# power_breakout.net
KiCad netlist of a schematic drawn in EAGLE
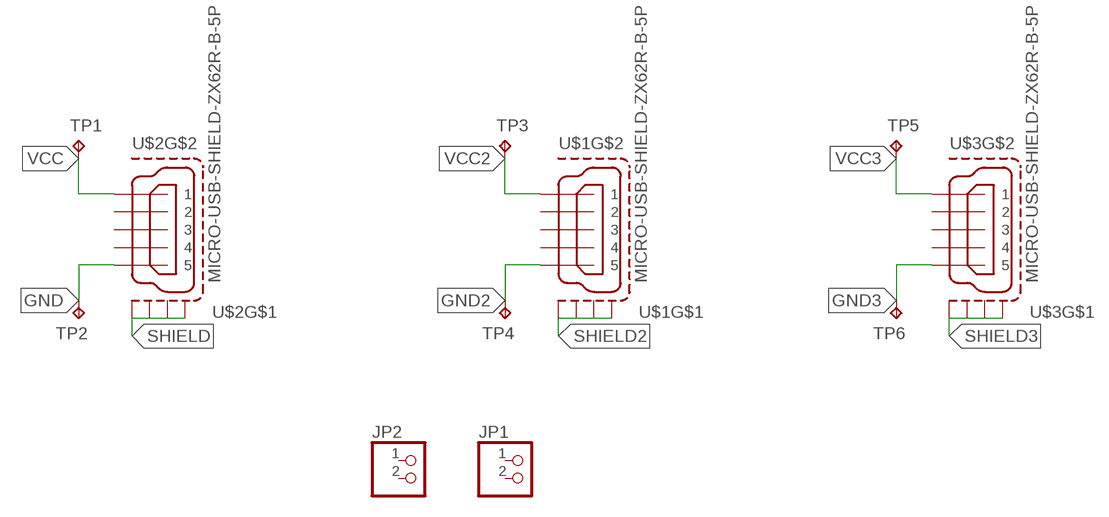
[diagram p0: schematic, sheet 1]

(export (version "E")
  (design (tool "Eeschema 10.0.6"))
  (components
    (comp (ref "JP1")
      (value "PINHD-1X2/90")
      (footprint "eagle-import:1X02_90")
      (libsource (lib "eagle-import") (part "PINHD-1X2/90"))
    )
    (comp (ref "JP2")
      (value "PINHD-1X2/90")
      (footprint "eagle-import:1X02_90")
      (libsource (lib "eagle-import") (part "PINHD-1X2/90"))
    )
    (comp (ref "TP1")
      (value "TPB1,27")
      (footprint "eagle-import:B1,27")
      (libsource (lib "eagle-import") (part "TPB1,27"))
    )
    (comp (ref "TP2")
      (value "TPB1,27")
      (footprint "eagle-import:B1,27")
      (libsource (lib "eagle-import") (part "TPB1,27"))
    )
    (comp (ref "TP3")
      (value "TPB1,27")
      (footprint "eagle-import:B1,27")
      (libsource (lib "eagle-import") (part "TPB1,27"))
    )
    (comp (ref "TP4")
      (value "TPB1,27")
      (footprint "eagle-import:B1,27")
      (libsource (lib "eagle-import") (part "TPB1,27"))
    )
    (comp (ref "TP5")
      (value "TPB1,27")
      (footprint "eagle-import:B1,27")
      (libsource (lib "eagle-import") (part "TPB1,27"))
    )
    (comp (ref "TP6")
      (value "TPB1,27")
      (footprint "eagle-import:B1,27")
      (libsource (lib "eagle-import") (part "TPB1,27"))
    )
    (comp (ref "U$1")
      (value "MICRO-USB-SHIELD-ZX62R-B-5P")
      (footprint "eagle-import:ZX62R-B-5P")
      (libsource (lib "eagle-import") (part "MICRO-USB-SHIELD-ZX62R-B-5P"))
    )
    (comp (ref "U$2")
      (value "MICRO-USB-SHIELD-ZX62R-B-5P")
      (footprint "eagle-import:ZX62R-B-5P")
      (libsource (lib "eagle-import") (part "MICRO-USB-SHIELD-ZX62R-B-5P"))
    )
    (comp (ref "U$3")
      (value "MICRO-USB-SHIELD-ZX62R-B-5P")
      (footprint "eagle-import:ZX62R-B-5P")
      (libsource (lib "eagle-import") (part "MICRO-USB-SHIELD-ZX62R-B-5P"))
    )
  )
  (nets
    (net (code "1") (name "GND") (class "Default")
      (node (ref "TP2") (pin "TP") (pinfunction "TP_TP") (pintype "input"))
      (node (ref "U$2") (pin "5") (pinfunction "5_5") (pintype "input"))
    )
    (net (code "2") (name "GND2") (class "Default")
      (node (ref "TP4") (pin "TP") (pinfunction "TP_TP") (pintype "input"))
      (node (ref "U$1") (pin "5") (pinfunction "5_5") (pintype "input"))
    )
    (net (code "3") (name "GND3") (class "Default")
      (node (ref "TP6") (pin "TP") (pinfunction "TP_TP") (pintype "input"))
      (node (ref "U$3") (pin "5") (pinfunction "5_5") (pintype "input"))
    )
    (net (code "4") (name "SHIELD") (class "Default")
      (node (ref "U$2") (pin "M1") (pinfunction "S1_M1") (pintype "passive"))
      (node (ref "U$2") (pin "M2") (pinfunction "S2_M2") (pintype "passive"))
      (node (ref "U$2") (pin "M3") (pinfunction "S3_M3") (pintype "passive"))
      (node (ref "U$2") (pin "M4") (pinfunction "S4_M4") (pintype "passive"))
    )
    (net (code "5") (name "SHIELD2") (class "Default")
      (node (ref "U$1") (pin "M1") (pinfunction "S1_M1") (pintype "passive"))
      (node (ref "U$1") (pin "M2") (pinfunction "S2_M2") (pintype "passive"))
      (node (ref "U$1") (pin "M3") (pinfunction "S3_M3") (pintype "passive"))
      (node (ref "U$1") (pin "M4") (pinfunction "S4_M4") (pintype "passive"))
    )
    (net (code "6") (name "SHIELD3") (class "Default")
      (node (ref "U$3") (pin "M1") (pinfunction "S1_M1") (pintype "passive"))
      (node (ref "U$3") (pin "M2") (pinfunction "S2_M2") (pintype "passive"))
      (node (ref "U$3") (pin "M3") (pinfunction "S3_M3") (pintype "passive"))
      (node (ref "U$3") (pin "M4") (pinfunction "S4_M4") (pintype "passive"))
    )
    (net (code "7") (name "VCC") (class "Default")
      (node (ref "TP1") (pin "TP") (pinfunction "TP_TP") (pintype "input"))
      (node (ref "U$2") (pin "1") (pinfunction "1_1") (pintype "input"))
    )
    (net (code "8") (name "VCC2") (class "Default")
      (node (ref "TP3") (pin "TP") (pinfunction "TP_TP") (pintype "input"))
      (node (ref "U$1") (pin "1") (pinfunction "1_1") (pintype "input"))
    )
    (net (code "9") (name "VCC3") (class "Default")
      (node (ref "TP5") (pin "TP") (pinfunction "TP_TP") (pintype "input"))
      (node (ref "U$3") (pin "1") (pinfunction "1_1") (pintype "input"))
    )
    (net (code "10") (name "unconnected-(JP1-Pad1)") (class "Default")
      (node (ref "JP1") (pin "1") (pinfunction "1_1") (pintype "passive"))
    )
    (net (code "11") (name "unconnected-(JP1-Pad2)") (class "Default")
      (node (ref "JP1") (pin "2") (pinfunction "2_2") (pintype "passive"))
    )
    (net (code "12") (name "unconnected-(JP2-Pad1)") (class "Default")
      (node (ref "JP2") (pin "1") (pinfunction "1_1") (pintype "passive"))
    )
    (net (code "13") (name "unconnected-(JP2-Pad2)") (class "Default")
      (node (ref "JP2") (pin "2") (pinfunction "2_2") (pintype "passive"))
    )
    (net (code "14") (name "unconnected-(U$1-Pad2)") (class "Default")
      (node (ref "U$1") (pin "2") (pinfunction "2_2") (pintype "input"))
    )
    (net (code "15") (name "unconnected-(U$1-Pad3)") (class "Default")
      (node (ref "U$1") (pin "3") (pinfunction "3_3") (pintype "input"))
    )
    (net (code "16") (name "unconnected-(U$1-Pad4)") (class "Default")
      (node (ref "U$1") (pin "4") (pinfunction "4_4") (pintype "input"))
    )
    (net (code "17") (name "unconnected-(U$2-Pad2)") (class "Default")
      (node (ref "U$2") (pin "2") (pinfunction "2_2") (pintype "input"))
    )
    (net (code "18") (name "unconnected-(U$2-Pad3)") (class "Default")
      (node (ref "U$2") (pin "3") (pinfunction "3_3") (pintype "input"))
    )
    (net (code "19") (name "unconnected-(U$2-Pad4)") (class "Default")
      (node (ref "U$2") (pin "4") (pinfunction "4_4") (pintype "input"))
    )
    (net (code "20") (name "unconnected-(U$3-Pad2)") (class "Default")
      (node (ref "U$3") (pin "2") (pinfunction "2_2") (pintype "input"))
    )
    (net (code "21") (name "unconnected-(U$3-Pad3)") (class "Default")
      (node (ref "U$3") (pin "3") (pinfunction "3_3") (pintype "input"))
    )
    (net (code "22") (name "unconnected-(U$3-Pad4)") (class "Default")
      (node (ref "U$3") (pin "4") (pinfunction "4_4") (pintype "input"))
    )
  )
)
